# pwr-breakout.net
KiCad netlist of a schematic drawn in EAGLE
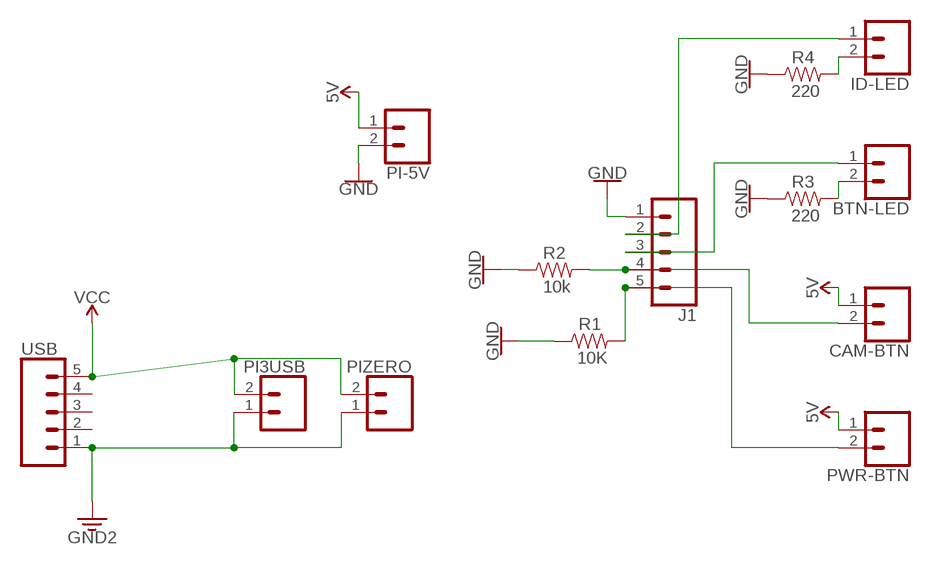
[diagram p0: schematic, sheet 1]

(export (version "E")
  (design (tool "Eeschema 10.0.6"))
  (components
    (comp (ref "BTN-LED")
      (value "CONN_021X02_NO_SILK")
      (footprint "eagle-import:1X02_NO_SILK")
      (libsource (lib "eagle-import") (part "CONN_021X02_NO_SILK"))
    )
    (comp (ref "CAM-BTN")
      (value "CONN_021X02_NO_SILK")
      (footprint "eagle-import:1X02_NO_SILK")
      (libsource (lib "eagle-import") (part "CONN_021X02_NO_SILK"))
    )
    (comp (ref "ID-LED")
      (value "CONN_021X02_NO_SILK")
      (footprint "eagle-import:1X02_NO_SILK")
      (libsource (lib "eagle-import") (part "CONN_021X02_NO_SILK"))
    )
    (comp (ref "J1")
      (value "CONN_05NO_SILK")
      (footprint "eagle-import:1X05_NO_SILK")
      (libsource (lib "eagle-import") (part "CONN_05NO_SILK"))
    )
    (comp (ref "PI-5V")
      (value "CONN_021X02_NO_SILK")
      (footprint "eagle-import:1X02_NO_SILK")
      (libsource (lib "eagle-import") (part "CONN_021X02_NO_SILK"))
    )
    (comp (ref "PI3USB")
      (value "CONN_021X02_NO_SILK")
      (footprint "eagle-import:1X02_NO_SILK")
      (libsource (lib "eagle-import") (part "CONN_021X02_NO_SILK"))
    )
    (comp (ref "PIZERO")
      (value "CONN_021X02_NO_SILK")
      (footprint "eagle-import:1X02_NO_SILK")
      (libsource (lib "eagle-import") (part "CONN_021X02_NO_SILK"))
    )
    (comp (ref "PWR-BTN")
      (value "CONN_021X02_NO_SILK")
      (footprint "eagle-import:1X02_NO_SILK")
      (libsource (lib "eagle-import") (part "CONN_021X02_NO_SILK"))
    )
    (comp (ref "R1")
      (value "10K")
      (footprint "eagle-import:AXIAL-0.3")
      (libsource (lib "eagle-import") (part "RESISTORAXIAL-0.3"))
    )
    (comp (ref "R2")
      (value "10k")
      (footprint "eagle-import:AXIAL-0.3")
      (libsource (lib "eagle-import") (part "RESISTORAXIAL-0.3"))
    )
    (comp (ref "R3")
      (value "220")
      (footprint "eagle-import:AXIAL-0.3")
      (libsource (lib "eagle-import") (part "RESISTORAXIAL-0.3"))
    )
    (comp (ref "R4")
      (value "220")
      (footprint "eagle-import:AXIAL-0.3")
      (libsource (lib "eagle-import") (part "RESISTORAXIAL-0.3"))
    )
    (comp (ref "USB")
      (value "CONN_05NO_SILK")
      (footprint "eagle-import:1X05_NO_SILK")
      (libsource (lib "eagle-import") (part "CONN_05NO_SILK"))
    )
  )
  (nets
    (net (code "1") (name "5V") (class "Default")
      (node (ref "CAM-BTN") (pin "1") (pinfunction "1_1") (pintype "passive"))
      (node (ref "PI-5V") (pin "1") (pinfunction "1_1") (pintype "passive"))
      (node (ref "PWR-BTN") (pin "1") (pinfunction "1_1") (pintype "passive"))
    )
    (net (code "2") (name "GND") (class "Default")
      (node (ref "J1") (pin "1") (pinfunction "1_1") (pintype "passive"))
      (node (ref "PI-5V") (pin "2") (pinfunction "2_2") (pintype "passive"))
      (node (ref "R1") (pin "P$1") (pinfunction "1_P$1") (pintype "passive"))
      (node (ref "R2") (pin "P$1") (pinfunction "1_P$1") (pintype "passive"))
      (node (ref "R3") (pin "P$1") (pinfunction "1_P$1") (pintype "passive"))
      (node (ref "R4") (pin "P$1") (pinfunction "1_P$1") (pintype "passive"))
    )
    (net (code "3") (name "GND2") (class "Default")
      (node (ref "PI3USB") (pin "1") (pinfunction "1_1") (pintype "passive"))
      (node (ref "PIZERO") (pin "1") (pinfunction "1_1") (pintype "passive"))
      (node (ref "USB") (pin "1") (pinfunction "1_1") (pintype "passive"))
    )
    (net (code "4") (name "Net-(BTN-LED-Pad1)") (class "Default")
      (node (ref "BTN-LED") (pin "1") (pinfunction "1_1") (pintype "passive"))
      (node (ref "J1") (pin "3") (pinfunction "3_3") (pintype "passive"))
    )
    (net (code "5") (name "Net-(ID-LED-Pad1)") (class "Default")
      (node (ref "ID-LED") (pin "1") (pinfunction "1_1") (pintype "passive"))
      (node (ref "J1") (pin "2") (pinfunction "2_2") (pintype "passive"))
    )
    (net (code "6") (name "Net-(R1-2)") (class "Default")
      (node (ref "J1") (pin "5") (pinfunction "5_5") (pintype "passive"))
      (node (ref "PWR-BTN") (pin "2") (pinfunction "2_2") (pintype "passive"))
      (node (ref "R1") (pin "P$2") (pinfunction "2_P$2") (pintype "passive"))
    )
    (net (code "7") (name "Net-(R2-2)") (class "Default")
      (node (ref "CAM-BTN") (pin "2") (pinfunction "2_2") (pintype "passive"))
      (node (ref "J1") (pin "4") (pinfunction "4_4") (pintype "passive"))
      (node (ref "R2") (pin "P$2") (pinfunction "2_P$2") (pintype "passive"))
    )
    (net (code "8") (name "Net-(R3-2)") (class "Default")
      (node (ref "BTN-LED") (pin "2") (pinfunction "2_2") (pintype "passive"))
      (node (ref "R3") (pin "P$2") (pinfunction "2_P$2") (pintype "passive"))
    )
    (net (code "9") (name "Net-(R4-2)") (class "Default")
      (node (ref "ID-LED") (pin "2") (pinfunction "2_2") (pintype "passive"))
      (node (ref "R4") (pin "P$2") (pinfunction "2_P$2") (pintype "passive"))
    )
    (net (code "10") (name "VCC") (class "Default")
      (node (ref "PI3USB") (pin "2") (pinfunction "2_2") (pintype "passive"))
      (node (ref "PIZERO") (pin "2") (pinfunction "2_2") (pintype "passive"))
      (node (ref "USB") (pin "5") (pinfunction "5_5") (pintype "passive"))
    )
    (net (code "11") (name "unconnected-(USB-Pad2)") (class "Default")
      (node (ref "USB") (pin "2") (pinfunction "2_2") (pintype "passive"))
    )
    (net (code "12") (name "unconnected-(USB-Pad3)") (class "Default")
      (node (ref "USB") (pin "3") (pinfunction "3_3") (pintype "passive"))
    )
    (net (code "13") (name "unconnected-(USB-Pad4)") (class "Default")
      (node (ref "USB") (pin "4") (pinfunction "4_4") (pintype "passive"))
    )
  )
)
